# 4_cyber60-smk_power.net
KiCad netlist of a schematic drawn in Altium Designer
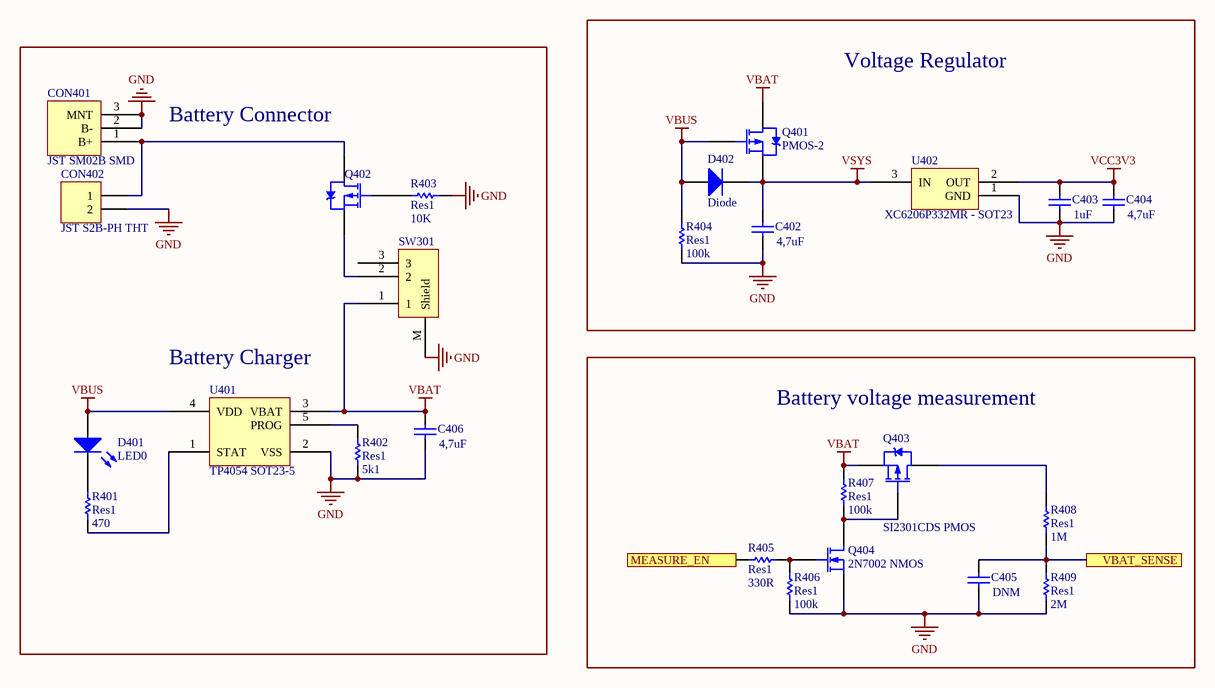
[diagram p0: 4_cyber60-smk_power.SchDoc]

(export (version "E")
  (design (tool "Eeschema 10.0.6"))
  (components
    (comp (ref "C402")
      (value "4,7uF")
      (footprint "C0603[1608]")
      (description "Capacitor")
      (fields (field (name "LCSC PART #") "C19666") (field (name "MRF.PART") "CL10A475KO8NNNC"))
      (libsource (lib "Miscellaneous Devices") (part "Cap"))
    )
    (comp (ref "C403")
      (value "1uF")
      (footprint "C0603[1608]")
      (description "Capacitor")
      (fields (field (name "MFG") "KEMET") (field (name "LCSC PART #") "C15849"))
      (libsource (lib "Miscellaneous Devices") (part "Cap"))
    )
    (comp (ref "C404")
      (value "4,7uF")
      (footprint "C0603[1608]")
      (description "Capacitor")
      (fields (field (name "LCSC PART #") "C19666") (field (name "MRF.PART") "CL10A475KO8NNNC"))
      (libsource (lib "Miscellaneous Devices") (part "Cap"))
    )
    (comp (ref "C405")
      (value "DNM")
      (footprint "C0603[1608]")
      (description "Capacitor")
      (libsource (lib "Miscellaneous Devices") (part "Cap"))
    )
    (comp (ref "C406")
      (value "4,7uF")
      (footprint "C0603[1608]")
      (description "Capacitor")
      (fields (field (name "LCSC PART #") "C19666") (field (name "MRF.PART") "CL10A475KO8NNNC"))
      (libsource (lib "Miscellaneous Devices") (part "Cap"))
    )
    (comp (ref "CON401")
      (value "JST SM02B SMD")
      (footprint "JST SM02B-SRSS-TB")
      (fields (field (name "LCSC PART #") "C160402") (field (name "MRF.PART") "SM02B-SRSS-TB(LF)(SN)"))
      (libsource (lib "Keebs") (part "JST S2B-PH-SM4-TB"))
    )
    (comp (ref "CON402")
      (value "JST S2B-PH THT")
      (footprint "Keebs:JST S2B-PH-K(LF)(SN)")
      (description "Header, 2-Pin")
      (fields (field (name "LCSC PART #") "C265016") (field (name "MRF.PART") "S2B-PH-K(LF)(SN)"))
      (libsource (lib "Miscellaneous Connectors") (part "Header 2"))
    )
    (comp (ref "D401")
      (value "LED0")
      (footprint "LED0603[1608]")
      (description "Typical INFRARED GaAs LED")
      (fields (field (name "LCSC PART #") "C72038") (field (name "MRF.PART") "19-213/Y2C-CQ2R2L/3T(CY)"))
      (libsource (lib "Miscellaneous Devices") (part "LED0"))
    )
    (comp (ref "D402")
      (value "Diode")
      (footprint "SOD-123")
      (description "Default Diode")
      (fields (field (name "LCSC PART #") "C8598") (field (name "MRF.PART") "B5819W"))
      (libsource (lib "Miscellaneous Devices") (part "Diode"))
    )
    (comp (ref "Q401")
      (value "PMOS-2")
      (footprint "SOT-23-3")
      (description "P-Channel Power MOSFET")
      (fields (field (name "MRF.PART") "SI2301CDS-T1-GE3") (field (name "LCSC PART #") "C10487"))
      (libsource (lib "Miscellaneous Devices") (part "PMOS-2"))
    )
    (comp (ref "Q402")
      (value "PMOS-2")
      (footprint "SOT-23-3")
      (description "P-Channel Power MOSFET")
      (fields (field (name "LCSC PART #") "C10487") (field (name "MRF.PART") "SI2301CDS-T1-GE3"))
      (libsource (lib "Miscellaneous Devices") (part "PMOS-2"))
    )
    (comp (ref "Q403")
      (value "SI2301CDS PMOS")
      (footprint "SOT-23-3")
      (description "P-Channel Power MOSFET")
      (fields (field (name "MRF.PART") "SI2301CDS-T1-GE3") (field (name "LCSC PART #") "C10487"))
      (libsource (lib "Miscellaneous Devices") (part "PMOS-2"))
    )
    (comp (ref "Q404")
      (value "2N7002 NMOS")
      (footprint "SOT-23-3")
      (description "N-Channel MOSFET")
      (fields (field (name "LCSC PART #") "C8545") (field (name "MRF.PART") "2N7002"))
      (libsource (lib "Miscellaneous Devices") (part "MOSFET-N"))
    )
    (comp (ref "R401")
      (value "Res1")
      (footprint "R0603[1608]")
      (description "Resistor")
      (fields
        (field (name "ALTIUM_VALUE") "470")
        (field (name "MFG") "Panasonic Electronic Components")
        (field (name "LCSC PART #") "C23179")
      )
      (libsource (lib "Miscellaneous Devices") (part "Res1"))
    )
    (comp (ref "R402")
      (value "Res1")
      (footprint "R0603[1608]")
      (description "Resistor")
      (fields
        (field (name "ALTIUM_VALUE") "5k1")
        (field (name "MFG") "Panasonic Electronic Components")
        (field (name "LCSC PART #") "C23186")
      )
      (libsource (lib "Miscellaneous Devices") (part "Res1"))
    )
    (comp (ref "R403")
      (value "Res1")
      (footprint "R0603[1608]")
      (description "Resistor")
      (fields
        (field (name "ALTIUM_VALUE") "10K")
        (field (name "MFG") "Panasonic Electronic Components")
        (field (name "LCSC PART #") "C25804")
      )
      (libsource (lib "Miscellaneous Devices") (part "Res1"))
    )
    (comp (ref "R404")
      (value "Res1")
      (footprint "R0603[1608]")
      (description "Resistor")
      (fields
        (field (name "ALTIUM_VALUE") "100k")
        (field (name "MRF.PART") "0603WAF1003T5E")
        (field (name "LCSC PART #") "C25803")
      )
      (libsource (lib "Miscellaneous Devices") (part "Res1"))
    )
    (comp (ref "R405")
      (value "Res1")
      (footprint "R0603[1608]")
      (description "Resistor")
      (fields
        (field (name "ALTIUM_VALUE") "330R")
        (field (name "LCSC PART #") "C23138")
        (field (name "MRF.PART") "0603WAF3300T5E")
      )
      (libsource (lib "Miscellaneous Devices") (part "Res1"))
    )
    (comp (ref "R406")
      (value "Res1")
      (footprint "R0603[1608]")
      (description "Resistor")
      (fields
        (field (name "ALTIUM_VALUE") "100k")
        (field (name "MRF.PART") "0603WAF1003T5E")
        (field (name "LCSC PART #") "C25803")
      )
      (libsource (lib "Miscellaneous Devices") (part "Res1"))
    )
    (comp (ref "R407")
      (value "Res1")
      (footprint "R0603[1608]")
      (description "Resistor")
      (fields
        (field (name "ALTIUM_VALUE") "100k")
        (field (name "MRF.PART") "0603WAF1003T5E")
        (field (name "LCSC PART #") "C25803")
      )
      (libsource (lib "Miscellaneous Devices") (part "Res1"))
    )
    (comp (ref "R408")
      (value "Res1")
      (footprint "R0603[1608]")
      (description "Resistor")
      (fields
        (field (name "ALTIUM_VALUE") "1M")
        (field (name "MRF.PART") "0603WAF1004T5E")
        (field (name "LCSC PART #") "C22935")
      )
      (libsource (lib "Miscellaneous Devices") (part "Res1"))
    )
    (comp (ref "R409")
      (value "Res1")
      (footprint "R0603[1608]")
      (description "Resistor")
      (fields
        (field (name "ALTIUM_VALUE") "2M")
        (field (name "MRF.PART") "0603WAF2004T5E")
        (field (name "LCSC PART #") "C22976")
      )
      (libsource (lib "Miscellaneous Devices") (part "Res1"))
    )
    (comp (ref "SW301")
      (value "Korean Hroparts Elec K3-1296S-E2")
      (footprint "Korean Hroparts Elec K3-1296S-E2")
      (fields (field (name "LCSC PART #") "C136659"))
      (libsource (lib "Keebs") (part "Korean Hroparts Elec K3-1296S-E2"))
    )
    (comp (ref "U401")
      (value "TP4054 SOT23-5")
      (footprint "SOT-23-5")
      (fields (field (name "LCSC PART #") "C32574") (field (name "MRF.PART") "TP4054"))
      (libsource (lib "Keebs") (part "MCP73831"))
    )
    (comp (ref "U402")
      (value "XC6206P332MR - SOT23")
      (footprint "SOT-23-3")
      (fields
        (field (name "LCSC PART #") "C5446")
        (field (name "MRF.PART") "XC6206P332MR")
        (field (name "MFG") "Texas Instruments")
      )
      (libsource (lib "Keebs") (part "SOT23 LDO"))
    )
  )
  (nets
    (net (code "1") (name "/MEASURE_EN") (class "Default")
      (node (ref "R405") (pin "1") (pinfunction "1_1") (pintype "passive"))
    )
    (net (code "2") (name "/VBAT_SENSE") (class "Default")
      (node (ref "C405") (pin "2") (pinfunction "2_2") (pintype "passive"))
      (node (ref "R408") (pin "2") (pinfunction "2_2") (pintype "passive"))
      (node (ref "R409") (pin "1") (pinfunction "1_1") (pintype "passive"))
    )
    (net (code "3") (name "GND") (class "Default")
      (node (ref "C402") (pin "1") (pinfunction "1_1") (pintype "passive"))
      (node (ref "C403") (pin "1") (pinfunction "1_1") (pintype "passive"))
      (node (ref "C404") (pin "1") (pinfunction "1_1") (pintype "passive"))
      (node (ref "C405") (pin "1") (pinfunction "1_1") (pintype "passive"))
      (node (ref "C406") (pin "1") (pinfunction "1_1") (pintype "passive"))
      (node (ref "CON401") (pin "2") (pinfunction "B-_2") (pintype "passive"))
      (node (ref "CON401") (pin "3") (pinfunction "MNT_3") (pintype "passive"))
      (node (ref "CON402") (pin "2") (pinfunction "2_2") (pintype "passive"))
      (node (ref "Q404") (pin "2") (pinfunction "S_2") (pintype "passive"))
      (node (ref "R402") (pin "2") (pinfunction "2_2") (pintype "passive"))
      (node (ref "R403") (pin "2") (pinfunction "2_2") (pintype "passive"))
      (node (ref "R404") (pin "2") (pinfunction "2_2") (pintype "passive"))
      (node (ref "R406") (pin "2") (pinfunction "2_2") (pintype "passive"))
      (node (ref "R409") (pin "2") (pinfunction "2_2") (pintype "passive"))
      (node (ref "SW301") (pin "M") (pinfunction "Shield_M") (pintype "passive"))
      (node (ref "U401") (pin "2") (pinfunction "VSS_2") (pintype "passive"))
      (node (ref "U402") (pin "1") (pinfunction "GND_1") (pintype "passive"))
    )
    (net (code "4") (name "Net-(CON401-B+)") (class "Default")
      (node (ref "CON401") (pin "1") (pinfunction "B+_1") (pintype "passive"))
      (node (ref "CON402") (pin "1") (pinfunction "1_1") (pintype "passive"))
      (node (ref "Q402") (pin "3") (pinfunction "D_3") (pintype "passive"))
    )
    (net (code "5") (name "Net-(D401-K)") (class "Default")
      (node (ref "D401") (pin "2") (pinfunction "K_2") (pintype "passive"))
      (node (ref "R401") (pin "2") (pinfunction "2_2") (pintype "passive"))
    )
    (net (code "6") (name "Net-(Q402-G)") (class "Default")
      (node (ref "Q402") (pin "1") (pinfunction "G_1") (pintype "passive"))
      (node (ref "R403") (pin "1") (pinfunction "1_1") (pintype "passive"))
    )
    (net (code "7") (name "Net-(Q402-S)") (class "Default")
      (node (ref "Q402") (pin "2") (pinfunction "S_2") (pintype "passive"))
      (node (ref "SW301") (pin "2") (pinfunction "2_2") (pintype "passive"))
    )
    (net (code "8") (name "Net-(Q403-D)") (class "Default")
      (node (ref "Q403") (pin "3") (pinfunction "D_3") (pintype "passive"))
      (node (ref "R408") (pin "1") (pinfunction "1_1") (pintype "passive"))
    )
    (net (code "9") (name "Net-(Q403-G)") (class "Default")
      (node (ref "Q403") (pin "1") (pinfunction "G_1") (pintype "passive"))
      (node (ref "Q404") (pin "3") (pinfunction "D_3") (pintype "passive"))
      (node (ref "R407") (pin "2") (pinfunction "2_2") (pintype "passive"))
    )
    (net (code "10") (name "Net-(Q404-G)") (class "Default")
      (node (ref "Q404") (pin "1") (pinfunction "G_1") (pintype "passive"))
      (node (ref "R405") (pin "2") (pinfunction "2_2") (pintype "passive"))
      (node (ref "R406") (pin "1") (pinfunction "1_1") (pintype "passive"))
    )
    (net (code "11") (name "Net-(U401-PROG)") (class "Default")
      (node (ref "R402") (pin "1") (pinfunction "1_1") (pintype "passive"))
      (node (ref "U401") (pin "5") (pinfunction "PROG_5") (pintype "passive"))
    )
    (net (code "12") (name "Net-(U401-STAT)") (class "Default")
      (node (ref "R401") (pin "1") (pinfunction "1_1") (pintype "passive"))
      (node (ref "U401") (pin "1") (pinfunction "STAT_1") (pintype "passive"))
    )
    (net (code "13") (name "VBAT") (class "Default")
      (node (ref "C406") (pin "2") (pinfunction "2_2") (pintype "passive"))
      (node (ref "Q401") (pin "3") (pinfunction "D_3") (pintype "passive"))
      (node (ref "Q403") (pin "2") (pinfunction "S_2") (pintype "passive"))
      (node (ref "R407") (pin "1") (pinfunction "1_1") (pintype "passive"))
      (node (ref "SW301") (pin "1") (pinfunction "1_1") (pintype "passive"))
      (node (ref "U401") (pin "3") (pinfunction "VBAT_3") (pintype "passive"))
    )
    (net (code "14") (name "VBUS") (class "Default")
      (node (ref "D401") (pin "1") (pinfunction "A_1") (pintype "passive"))
      (node (ref "D402") (pin "1") (pinfunction "A_1") (pintype "passive"))
      (node (ref "Q401") (pin "1") (pinfunction "G_1") (pintype "passive"))
      (node (ref "R404") (pin "1") (pinfunction "1_1") (pintype "passive"))
      (node (ref "U401") (pin "4") (pinfunction "VDD_4") (pintype "passive"))
    )
    (net (code "15") (name "VCC3V3") (class "Default")
      (node (ref "C403") (pin "2") (pinfunction "2_2") (pintype "passive"))
      (node (ref "C404") (pin "2") (pinfunction "2_2") (pintype "passive"))
      (node (ref "U402") (pin "2") (pinfunction "OUT_2") (pintype "passive"))
    )
    (net (code "16") (name "VSYS") (class "Default")
      (node (ref "C402") (pin "2") (pinfunction "2_2") (pintype "passive"))
      (node (ref "D402") (pin "2") (pinfunction "K_2") (pintype "passive"))
      (node (ref "Q401") (pin "2") (pinfunction "S_2") (pintype "passive"))
      (node (ref "U402") (pin "3") (pinfunction "IN_3") (pintype "passive"))
    )
    (net (code "17") (name "unconnected-(SW301-Pad3)") (class "Default")
      (node (ref "SW301") (pin "3") (pinfunction "3_3") (pintype "passive"))
    )
  )
)
